# USB_-_UART_link.net
KiCad netlist of a schematic drawn in EAGLE
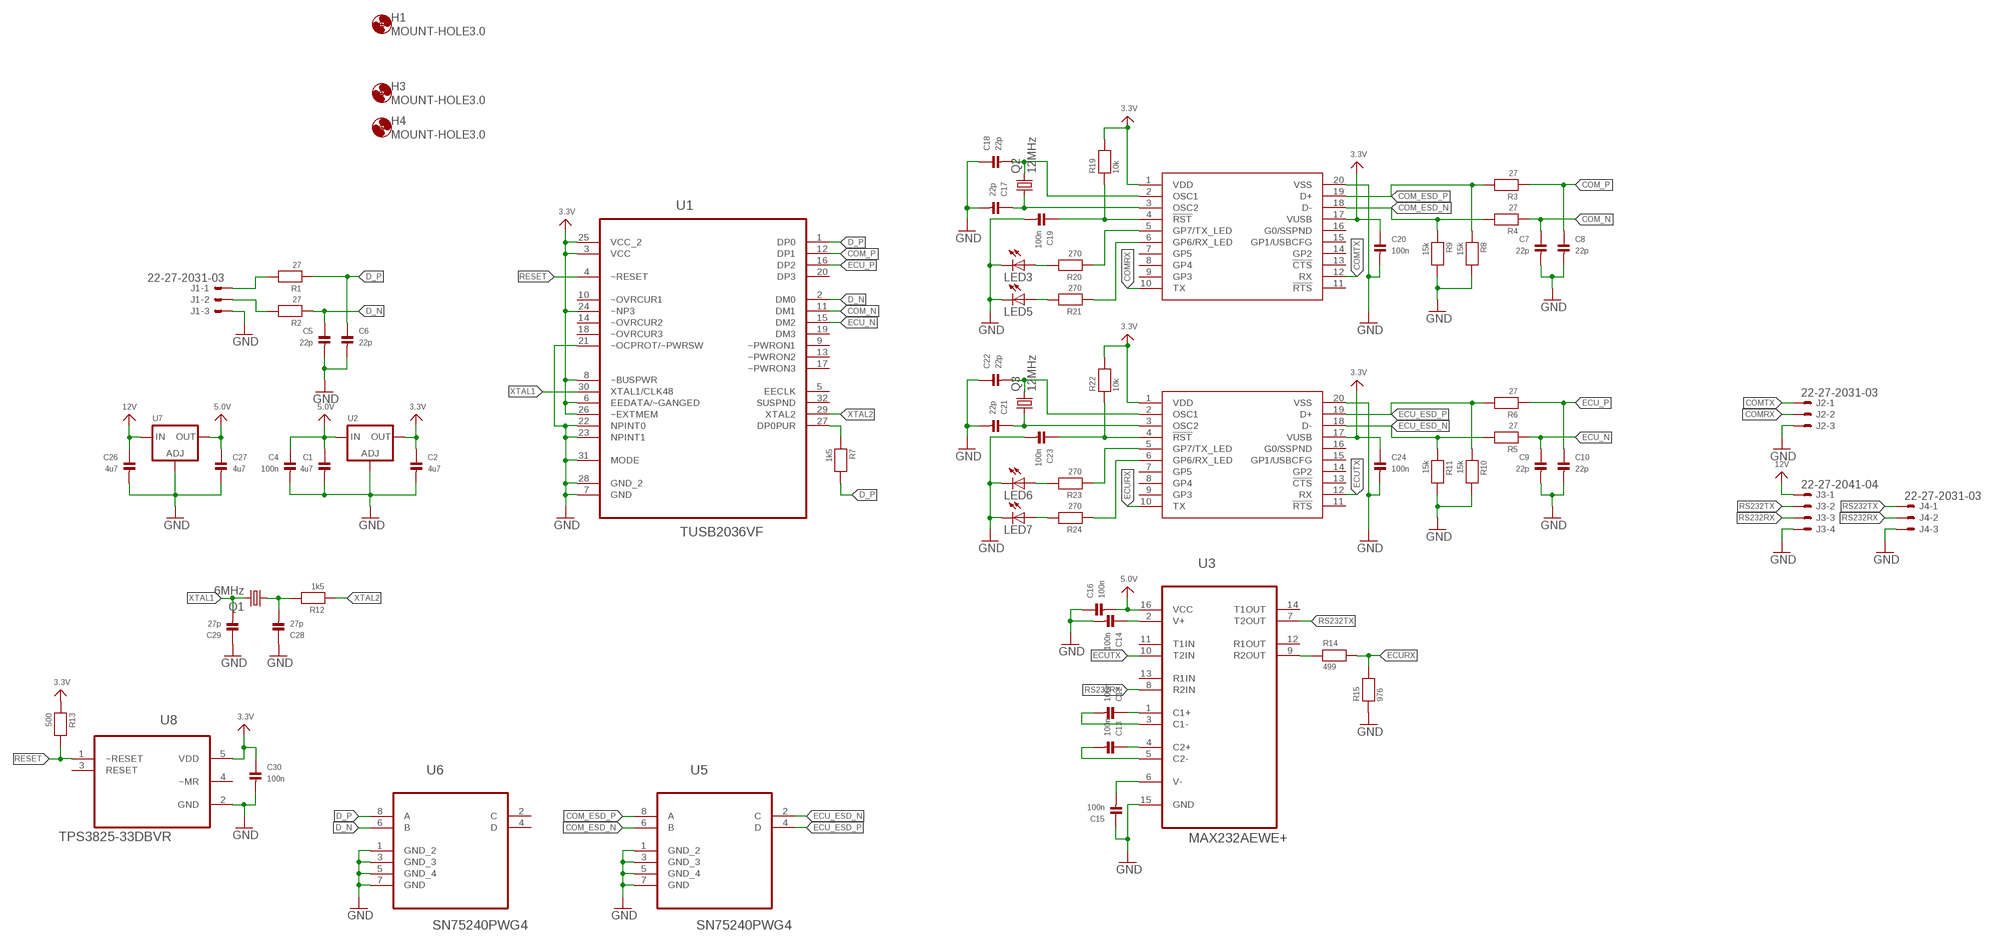
[diagram p0: schematic, sheet 1]

(export (version "E")
  (design (tool "Eeschema 10.0.6"))
  (components
    (comp (ref "C1")
      (value "4u7")
      (footprint "eagle-import:_0805")
      (libsource (lib "eagle-import") (part "CAP_CERAMIC_0805"))
    )
    (comp (ref "C2")
      (value "4u7")
      (footprint "eagle-import:_0805")
      (libsource (lib "eagle-import") (part "CAP_CERAMIC_0805"))
    )
    (comp (ref "C4")
      (value "100n")
      (footprint "eagle-import:_0603")
      (libsource (lib "eagle-import") (part "CAP_CERAMIC_0603"))
    )
    (comp (ref "C5")
      (value "22p")
      (footprint "eagle-import:_0603")
      (libsource (lib "eagle-import") (part "CAP_CERAMIC_0603"))
    )
    (comp (ref "C6")
      (value "22p")
      (footprint "eagle-import:_0603")
      (libsource (lib "eagle-import") (part "CAP_CERAMIC_0603"))
    )
    (comp (ref "C7")
      (value "22p")
      (footprint "eagle-import:_0603")
      (libsource (lib "eagle-import") (part "CAP_CERAMIC_0603"))
    )
    (comp (ref "C8")
      (value "22p")
      (footprint "eagle-import:_0603")
      (libsource (lib "eagle-import") (part "CAP_CERAMIC_0603"))
    )
    (comp (ref "C9")
      (value "22p")
      (footprint "eagle-import:_0603")
      (libsource (lib "eagle-import") (part "CAP_CERAMIC_0603"))
    )
    (comp (ref "C10")
      (value "22p")
      (footprint "eagle-import:_0603")
      (libsource (lib "eagle-import") (part "CAP_CERAMIC_0603"))
    )
    (comp (ref "C12")
      (value "100n")
      (footprint "eagle-import:_0603")
      (libsource (lib "eagle-import") (part "CAP_CERAMIC_0603"))
    )
    (comp (ref "C13")
      (value "100n")
      (footprint "eagle-import:_0603")
      (libsource (lib "eagle-import") (part "CAP_CERAMIC_0603"))
    )
    (comp (ref "C14")
      (value "100n")
      (footprint "eagle-import:_0603")
      (libsource (lib "eagle-import") (part "CAP_CERAMIC_0603"))
    )
    (comp (ref "C15")
      (value "100n")
      (footprint "eagle-import:_0603")
      (libsource (lib "eagle-import") (part "CAP_CERAMIC_0603"))
    )
    (comp (ref "C16")
      (value "100n")
      (footprint "eagle-import:_0603")
      (libsource (lib "eagle-import") (part "CAP_CERAMIC_0603"))
    )
    (comp (ref "C17")
      (value "22p")
      (footprint "eagle-import:_0603")
      (libsource (lib "eagle-import") (part "CAP_CERAMIC_0603"))
    )
    (comp (ref "C18")
      (value "22p")
      (footprint "eagle-import:_0603")
      (libsource (lib "eagle-import") (part "CAP_CERAMIC_0603"))
    )
    (comp (ref "C19")
      (value "100n")
      (footprint "eagle-import:_0603")
      (libsource (lib "eagle-import") (part "CAP_CERAMIC_0603"))
    )
    (comp (ref "C20")
      (value "100n")
      (footprint "eagle-import:_0603")
      (libsource (lib "eagle-import") (part "CAP_CERAMIC_0603"))
    )
    (comp (ref "C21")
      (value "22p")
      (footprint "eagle-import:_0603")
      (libsource (lib "eagle-import") (part "CAP_CERAMIC_0603"))
    )
    (comp (ref "C22")
      (value "22p")
      (footprint "eagle-import:_0603")
      (libsource (lib "eagle-import") (part "CAP_CERAMIC_0603"))
    )
    (comp (ref "C23")
      (value "100n")
      (footprint "eagle-import:_0603")
      (libsource (lib "eagle-import") (part "CAP_CERAMIC_0603"))
    )
    (comp (ref "C24")
      (value "100n")
      (footprint "eagle-import:_0603")
      (libsource (lib "eagle-import") (part "CAP_CERAMIC_0603"))
    )
    (comp (ref "C26")
      (value "4u7")
      (footprint "eagle-import:_0805")
      (libsource (lib "eagle-import") (part "CAP_CERAMIC_0805"))
    )
    (comp (ref "C27")
      (value "4u7")
      (footprint "eagle-import:_0805")
      (libsource (lib "eagle-import") (part "CAP_CERAMIC_0805"))
    )
    (comp (ref "C28")
      (value "27p")
      (footprint "eagle-import:_0603")
      (libsource (lib "eagle-import") (part "CAP_CERAMIC_0603"))
    )
    (comp (ref "C29")
      (value "27p")
      (footprint "eagle-import:_0603")
      (libsource (lib "eagle-import") (part "CAP_CERAMIC_0603"))
    )
    (comp (ref "C30")
      (value "100n")
      (footprint "eagle-import:_0603")
      (libsource (lib "eagle-import") (part "CAP_CERAMIC_0603"))
    )
    (comp (ref "H1")
      (value "MOUNT-HOLE3.0")
      (footprint "eagle-import:3,0")
      (libsource (lib "eagle-import") (part "MOUNT-HOLE3.0"))
    )
    (comp (ref "H3")
      (value "MOUNT-HOLE3.0")
      (footprint "eagle-import:3,0")
      (libsource (lib "eagle-import") (part "MOUNT-HOLE3.0"))
    )
    (comp (ref "H4")
      (value "MOUNT-HOLE3.0")
      (footprint "eagle-import:3,0")
      (libsource (lib "eagle-import") (part "MOUNT-HOLE3.0"))
    )
    (comp (ref "J1")
      (value "22-27-2031-03")
      (footprint "eagle-import:6410-03")
      (libsource (lib "eagle-import") (part "22-?-0327-2031"))
    )
    (comp (ref "J2")
      (value "22-27-2031-03")
      (footprint "eagle-import:6410-03")
      (libsource (lib "eagle-import") (part "22-?-0327-2031"))
    )
    (comp (ref "J3")
      (value "22-27-2041-04")
      (footprint "eagle-import:6410-04")
      (libsource (lib "eagle-import") (part "22-?-0427-2041"))
    )
    (comp (ref "J4")
      (value "22-27-2031-03")
      (footprint "eagle-import:6410-03")
      (libsource (lib "eagle-import") (part "22-?-0327-2031"))
    )
    (comp (ref "LED3")
      (value "LEDCHIPLED_0805")
      (footprint "eagle-import:CHIPLED_0805")
      (libsource (lib "eagle-import") (part "LEDCHIPLED_0805"))
    )
    (comp (ref "LED5")
      (value "LEDCHIPLED_0805")
      (footprint "eagle-import:CHIPLED_0805")
      (libsource (lib "eagle-import") (part "LEDCHIPLED_0805"))
    )
    (comp (ref "LED6")
      (value "LEDCHIPLED_0805")
      (footprint "eagle-import:CHIPLED_0805")
      (libsource (lib "eagle-import") (part "LEDCHIPLED_0805"))
    )
    (comp (ref "LED7")
      (value "LEDCHIPLED_0805")
      (footprint "eagle-import:CHIPLED_0805")
      (libsource (lib "eagle-import") (part "LEDCHIPLED_0805"))
    )
    (comp (ref "Q1")
      (value "6MHz")
      (footprint "eagle-import:HC49_S")
      (libsource (lib "eagle-import") (part "CRYSTALHC49S"))
    )
    (comp (ref "Q2")
      (value "12MHz")
      (footprint "eagle-import:HC49_S")
      (libsource (lib "eagle-import") (part "CRYSTALHC49S"))
    )
    (comp (ref "Q3")
      (value "12MHz")
      (footprint "eagle-import:HC49_S")
      (libsource (lib "eagle-import") (part "CRYSTALHC49S"))
    )
    (comp (ref "R1")
      (value "27")
      (footprint "eagle-import:_0603")
      (libsource (lib "eagle-import") (part "RESISTOR_0603"))
    )
    (comp (ref "R2")
      (value "27")
      (footprint "eagle-import:_0603")
      (libsource (lib "eagle-import") (part "RESISTOR_0603"))
    )
    (comp (ref "R3")
      (value "27")
      (footprint "eagle-import:_0603")
      (libsource (lib "eagle-import") (part "RESISTOR_0603"))
    )
    (comp (ref "R4")
      (value "27")
      (footprint "eagle-import:_0603")
      (libsource (lib "eagle-import") (part "RESISTOR_0603"))
    )
    (comp (ref "R5")
      (value "27")
      (footprint "eagle-import:_0603")
      (libsource (lib "eagle-import") (part "RESISTOR_0603"))
    )
    (comp (ref "R6")
      (value "27")
      (footprint "eagle-import:_0603")
      (libsource (lib "eagle-import") (part "RESISTOR_0603"))
    )
    (comp (ref "R7")
      (value "1k5")
      (footprint "eagle-import:_0603")
      (libsource (lib "eagle-import") (part "RESISTOR_0603"))
    )
    (comp (ref "R8")
      (value "15k")
      (footprint "eagle-import:_0603")
      (libsource (lib "eagle-import") (part "RESISTOR_0603"))
    )
    (comp (ref "R9")
      (value "15k")
      (footprint "eagle-import:_0603")
      (libsource (lib "eagle-import") (part "RESISTOR_0603"))
    )
    (comp (ref "R10")
      (value "15k")
      (footprint "eagle-import:_0603")
      (libsource (lib "eagle-import") (part "RESISTOR_0603"))
    )
    (comp (ref "R11")
      (value "15k")
      (footprint "eagle-import:_0603")
      (libsource (lib "eagle-import") (part "RESISTOR_0603"))
    )
    (comp (ref "R12")
      (value "1k5")
      (footprint "eagle-import:_0603")
      (libsource (lib "eagle-import") (part "RESISTOR_0603"))
    )
    (comp (ref "R13")
      (value "500")
      (footprint "eagle-import:_0603")
      (libsource (lib "eagle-import") (part "RESISTOR_0603"))
    )
    (comp (ref "R14")
      (value "499")
      (footprint "eagle-import:_0603")
      (libsource (lib "eagle-import") (part "RESISTOR_0603"))
    )
    (comp (ref "R15")
      (value "976")
      (footprint "eagle-import:_0603")
      (libsource (lib "eagle-import") (part "RESISTOR_0603"))
    )
    (comp (ref "R19")
      (value "10k")
      (footprint "eagle-import:_0603")
      (libsource (lib "eagle-import") (part "RESISTOR_0603"))
    )
    (comp (ref "R20")
      (value "270")
      (footprint "eagle-import:_0603")
      (libsource (lib "eagle-import") (part "RESISTOR_0603"))
    )
    (comp (ref "R21")
      (value "270")
      (footprint "eagle-import:_0603")
      (libsource (lib "eagle-import") (part "RESISTOR_0603"))
    )
    (comp (ref "R22")
      (value "10k")
      (footprint "eagle-import:_0603")
      (libsource (lib "eagle-import") (part "RESISTOR_0603"))
    )
    (comp (ref "R23")
      (value "270")
      (footprint "eagle-import:_0603")
      (libsource (lib "eagle-import") (part "RESISTOR_0603"))
    )
    (comp (ref "R24")
      (value "270")
      (footprint "eagle-import:_0603")
      (libsource (lib "eagle-import") (part "RESISTOR_0603"))
    )
    (comp (ref "U$24")
      (value "MCP2200")
      (footprint "eagle-import:SO20L")
      (libsource (lib "eagle-import") (part "MCP2200"))
    )
    (comp (ref "U$29")
      (value "MCP2200")
      (footprint "eagle-import:SO20L")
      (libsource (lib "eagle-import") (part "MCP2200"))
    )
    (comp (ref "U1")
      (value "TUSB2036VF")
      (footprint "eagle-import:QFP80P900X900X145-32N")
      (libsource (lib "eagle-import") (part "TUSB2036VF"))
    )
    (comp (ref "U2")
      (value "LM1117SOT223-REFLOW")
      (footprint "eagle-import:SOT223-R")
      (libsource (lib "eagle-import") (part "LM1117SOT223-REFLOW"))
    )
    (comp (ref "U3")
      (value "MAX232AEWE+")
      (footprint "eagle-import:SOIC127P1032X265-16N")
      (libsource (lib "eagle-import") (part "MAX232AEWE+"))
    )
    (comp (ref "U5")
      (value "SN75240PWG4")
      (footprint "eagle-import:SOP65P640X120-8N")
      (libsource (lib "eagle-import") (part "SN75240PWG4"))
    )
    (comp (ref "U6")
      (value "SN75240PWG4")
      (footprint "eagle-import:SOP65P640X120-8N")
      (libsource (lib "eagle-import") (part "SN75240PWG4"))
    )
    (comp (ref "U7")
      (value "LM1117SOT223-REFLOW")
      (footprint "eagle-import:SOT223-R")
      (libsource (lib "eagle-import") (part "LM1117SOT223-REFLOW"))
    )
    (comp (ref "U8")
      (value "TPS3825-33DBVR")
      (footprint "eagle-import:SOT95P280X145-5N")
      (libsource (lib "eagle-import") (part "TPS3825-33DBVR"))
    )
  )
  (nets
    (net (code "1") (name "3.3V") (class "Default")
      (node (ref "C2") (pin "1") (pinfunction "P$1_1") (pintype "passive"))
      (node (ref "C20") (pin "1") (pinfunction "P$1_1") (pintype "passive"))
      (node (ref "C24") (pin "1") (pinfunction "P$1_1") (pintype "passive"))
      (node (ref "C30") (pin "1") (pinfunction "P$1_1") (pintype "passive"))
      (node (ref "R13") (pin "1") (pinfunction "1_1") (pintype "passive"))
      (node (ref "R19") (pin "2") (pinfunction "2_2") (pintype "passive"))
      (node (ref "R22") (pin "2") (pinfunction "2_2") (pintype "passive"))
      (node (ref "U$24") (pin "1") (pinfunction "VDD_1") (pintype "bidirectional"))
      (node (ref "U$24") (pin "17") (pinfunction "VUSB_17") (pintype "bidirectional"))
      (node (ref "U$29") (pin "1") (pinfunction "VDD_1") (pintype "bidirectional"))
      (node (ref "U$29") (pin "17") (pinfunction "VUSB_17") (pintype "bidirectional"))
      (node (ref "U1") (pin "24") (pinfunction "~{NP3}_24") (pintype "input"))
      (node (ref "U1") (pin "25") (pinfunction "VCC_2_25") (pintype "power_in"))
      (node (ref "U1") (pin "26") (pinfunction "~{EXTMEM}_26") (pintype "input"))
      (node (ref "U1") (pin "3") (pinfunction "VCC_3") (pintype "power_in"))
      (node (ref "U1") (pin "6") (pinfunction "EEDATA/~{GANGED}_6") (pintype "bidirectional"))
      (node (ref "U1") (pin "8") (pinfunction "~{BUSPWR}_8") (pintype "input"))
      (node (ref "U2") (pin "2") (pinfunction "OUT_2") (pintype "passive"))
      (node (ref "U8") (pin "5") (pinfunction "VDD_5") (pintype "power_in"))
    )
    (net (code "2") (name "5.0V") (class "Default")
      (node (ref "C1") (pin "1") (pinfunction "P$1_1") (pintype "passive"))
      (node (ref "C16") (pin "2") (pinfunction "P$2_2") (pintype "passive"))
      (node (ref "C27") (pin "1") (pinfunction "P$1_1") (pintype "passive"))
      (node (ref "C4") (pin "1") (pinfunction "P$1_1") (pintype "passive"))
      (node (ref "U2") (pin "3") (pinfunction "IN_3") (pintype "input"))
      (node (ref "U3") (pin "16") (pinfunction "VCC_16") (pintype "power_in"))
      (node (ref "U7") (pin "2") (pinfunction "OUT_2") (pintype "passive"))
    )
    (net (code "3") (name "12V") (class "Default")
      (node (ref "C26") (pin "1") (pinfunction "P$1_1") (pintype "passive"))
      (node (ref "J3") (pin "1") (pinfunction "S_1") (pintype "passive"))
      (node (ref "U7") (pin "3") (pinfunction "IN_3") (pintype "input"))
    )
    (net (code "4") (name "COMRX") (class "Default")
      (node (ref "J2") (pin "2") (pinfunction "S_2") (pintype "passive"))
      (node (ref "U$24") (pin "10") (pinfunction "TX_10") (pintype "bidirectional"))
    )
    (net (code "5") (name "COMTX") (class "Default")
      (node (ref "J2") (pin "1") (pinfunction "S_1") (pintype "passive"))
      (node (ref "U$24") (pin "12") (pinfunction "RX_12") (pintype "bidirectional"))
    )
    (net (code "6") (name "COM_ESD_N") (class "Default")
      (node (ref "R4") (pin "2") (pinfunction "2_2") (pintype "passive"))
      (node (ref "R9") (pin "1") (pinfunction "1_1") (pintype "passive"))
      (node (ref "U$24") (pin "18") (pinfunction "D-_18") (pintype "bidirectional"))
      (node (ref "U5") (pin "6") (pinfunction "B_6") (pintype "passive"))
    )
    (net (code "7") (name "COM_ESD_P") (class "Default")
      (node (ref "R3") (pin "2") (pinfunction "2_2") (pintype "passive"))
      (node (ref "R8") (pin "1") (pinfunction "1_1") (pintype "passive"))
      (node (ref "U$24") (pin "19") (pinfunction "D+_19") (pintype "bidirectional"))
      (node (ref "U5") (pin "8") (pinfunction "A_8") (pintype "passive"))
    )
    (net (code "8") (name "COM_N") (class "Default")
      (node (ref "C7") (pin "1") (pinfunction "P$1_1") (pintype "passive"))
      (node (ref "R4") (pin "1") (pinfunction "1_1") (pintype "passive"))
      (node (ref "U1") (pin "11") (pinfunction "DM1_11") (pintype "bidirectional"))
    )
    (net (code "9") (name "COM_P") (class "Default")
      (node (ref "C8") (pin "1") (pinfunction "P$1_1") (pintype "passive"))
      (node (ref "R3") (pin "1") (pinfunction "1_1") (pintype "passive"))
      (node (ref "U1") (pin "12") (pinfunction "DP1_12") (pintype "bidirectional"))
    )
    (net (code "10") (name "D_N") (class "Default")
      (node (ref "C5") (pin "1") (pinfunction "P$1_1") (pintype "passive"))
      (node (ref "R2") (pin "1") (pinfunction "1_1") (pintype "passive"))
      (node (ref "U1") (pin "2") (pinfunction "DM0_2") (pintype "bidirectional"))
      (node (ref "U6") (pin "6") (pinfunction "B_6") (pintype "passive"))
    )
    (net (code "11") (name "D_P") (class "Default")
      (node (ref "C6") (pin "1") (pinfunction "P$1_1") (pintype "passive"))
      (node (ref "R1") (pin "1") (pinfunction "1_1") (pintype "passive"))
      (node (ref "R7") (pin "2") (pinfunction "2_2") (pintype "passive"))
      (node (ref "U1") (pin "1") (pinfunction "DP0_1") (pintype "bidirectional"))
      (node (ref "U6") (pin "8") (pinfunction "A_8") (pintype "passive"))
    )
    (net (code "12") (name "ECURX") (class "Default")
      (node (ref "R14") (pin "2") (pinfunction "2_2") (pintype "passive"))
      (node (ref "R15") (pin "2") (pinfunction "2_2") (pintype "passive"))
      (node (ref "U$29") (pin "10") (pinfunction "TX_10") (pintype "bidirectional"))
    )
    (net (code "13") (name "ECUTX") (class "Default")
      (node (ref "U$29") (pin "12") (pinfunction "RX_12") (pintype "bidirectional"))
      (node (ref "U3") (pin "10") (pinfunction "T2IN_10") (pintype "input"))
    )
    (net (code "14") (name "ECU_ESD_N") (class "Default")
      (node (ref "R11") (pin "1") (pinfunction "1_1") (pintype "passive"))
      (node (ref "R5") (pin "2") (pinfunction "2_2") (pintype "passive"))
      (node (ref "U$29") (pin "18") (pinfunction "D-_18") (pintype "bidirectional"))
      (node (ref "U5") (pin "2") (pinfunction "C_2") (pintype "passive"))
    )
    (net (code "15") (name "ECU_ESD_P") (class "Default")
      (node (ref "R10") (pin "1") (pinfunction "1_1") (pintype "passive"))
      (node (ref "R6") (pin "2") (pinfunction "2_2") (pintype "passive"))
      (node (ref "U$29") (pin "19") (pinfunction "D+_19") (pintype "bidirectional"))
      (node (ref "U5") (pin "4") (pinfunction "D_4") (pintype "passive"))
    )
    (net (code "16") (name "ECU_N") (class "Default")
      (node (ref "C9") (pin "1") (pinfunction "P$1_1") (pintype "passive"))
      (node (ref "R5") (pin "1") (pinfunction "1_1") (pintype "passive"))
      (node (ref "U1") (pin "15") (pinfunction "DM2_15") (pintype "bidirectional"))
    )
    (net (code "17") (name "ECU_P") (class "Default")
      (node (ref "C10") (pin "1") (pinfunction "P$1_1") (pintype "passive"))
      (node (ref "R6") (pin "1") (pinfunction "1_1") (pintype "passive"))
      (node (ref "U1") (pin "16") (pinfunction "DP2_16") (pintype "bidirectional"))
    )
    (net (code "18") (name "GND") (class "Default")
      (node (ref "C1") (pin "2") (pinfunction "P$2_2") (pintype "passive"))
      (node (ref "C10") (pin "2") (pinfunction "P$2_2") (pintype "passive"))
      (node (ref "C14") (pin "2") (pinfunction "P$2_2") (pintype "passive"))
      (node (ref "C15") (pin "1") (pinfunction "P$1_1") (pintype "passive"))
      (node (ref "C16") (pin "1") (pinfunction "P$1_1") (pintype "passive"))
      (node (ref "C17") (pin "2") (pinfunction "P$2_2") (pintype "passive"))
      (node (ref "C18") (pin "1") (pinfunction "P$1_1") (pintype "passive"))
      (node (ref "C19") (pin "2") (pinfunction "P$2_2") (pintype "passive"))
      (node (ref "C2") (pin "2") (pinfunction "P$2_2") (pintype "passive"))
      (node (ref "C20") (pin "2") (pinfunction "P$2_2") (pintype "passive"))
      (node (ref "C21") (pin "2") (pinfunction "P$2_2") (pintype "passive"))
      (node (ref "C22") (pin "1") (pinfunction "P$1_1") (pintype "passive"))
      (node (ref "C23") (pin "2") (pinfunction "P$2_2") (pintype "passive"))
      (node (ref "C24") (pin "2") (pinfunction "P$2_2") (pintype "passive"))
      (node (ref "C26") (pin "2") (pinfunction "P$2_2") (pintype "passive"))
      (node (ref "C27") (pin "2") (pinfunction "P$2_2") (pintype "passive"))
      (node (ref "C28") (pin "1") (pinfunction "P$1_1") (pintype "passive"))
      (node (ref "C29") (pin "1") (pinfunction "P$1_1") (pintype "passive"))
      (node (ref "C30") (pin "2") (pinfunction "P$2_2") (pintype "passive"))
      (node (ref "C4") (pin "2") (pinfunction "P$2_2") (pintype "passive"))
      (node (ref "C5") (pin "2") (pinfunction "P$2_2") (pintype "passive"))
      (node (ref "C6") (pin "2") (pinfunction "P$2_2") (pintype "passive"))
      (node (ref "C7") (pin "2") (pinfunction "P$2_2") (pintype "passive"))
      (node (ref "C8") (pin "2") (pinfunction "P$2_2") (pintype "passive"))
      (node (ref "C9") (pin "2") (pinfunction "P$2_2") (pintype "passive"))
      (node (ref "J1") (pin "3") (pinfunction "S_3") (pintype "passive"))
      (node (ref "J2") (pin "3") (pinfunction "S_3") (pintype "passive"))
      (node (ref "J3") (pin "4") (pinfunction "S_4") (pintype "passive"))
      (node (ref "J4") (pin "3") (pinfunction "S_3") (pintype "passive"))
      (node (ref "LED3") (pin "C") (pinfunction "C_C") (pintype "passive"))
      (node (ref "LED5") (pin "C") (pinfunction "C_C") (pintype "passive"))
      (node (ref "LED6") (pin "C") (pinfunction "C_C") (pintype "passive"))
      (node (ref "LED7") (pin "C") (pinfunction "C_C") (pintype "passive"))
      (node (ref "R10") (pin "2") (pinfunction "2_2") (pintype "passive"))
      (node (ref "R11") (pin "2") (pinfunction "2_2") (pintype "passive"))
      (node (ref "R15") (pin "1") (pinfunction "1_1") (pintype "passive"))
      (node (ref "R8") (pin "2") (pinfunction "2_2") (pintype "passive"))
      (node (ref "R9") (pin "2") (pinfunction "2_2") (pintype "passive"))
      (node (ref "U$24") (pin "20") (pinfunction "VSS_20") (pintype "bidirectional"))
      (node (ref "U$29") (pin "20") (pinfunction "VSS_20") (pintype "bidirectional"))
      (node (ref "U1") (pin "21") (pinfunction "~{OCPROT/}PWRSW_21") (pintype "input"))
      (node (ref "U1") (pin "22") (pinfunction "NPINT0_22") (pintype "input"))
      (node (ref "U1") (pin "23") (pinfunction "NPINT1_23") (pintype "input"))
      (node (ref "U1") (pin "28") (pinfunction "GND_2_28") (pintype "passive"))
      (node (ref "U1") (pin "31") (pinfunction "MODE_31") (pintype "input"))
      (node (ref "U1") (pin "7") (pinfunction "GND_7") (pintype "passive"))
      (node (ref "U2") (pin "1") (pinfunction "ADJ_1") (pintype "input"))
      (node (ref "U3") (pin "15") (pinfunction "GND_15") (pintype "passive"))
      (node (ref "U5") (pin "1") (pinfunction "GND_2_1") (pintype "passive"))
      (node (ref "U5") (pin "3") (pinfunction "GND_3_3") (pintype "passive"))
      (node (ref "U5") (pin "5") (pinfunction "GND_4_5") (pintype "passive"))
      (node (ref "U5") (pin "7") (pinfunction "GND_7") (pintype "passive"))
      (node (ref "U6") (pin "1") (pinfunction "GND_2_1") (pintype "passive"))
      (node (ref "U6") (pin "3") (pinfunction "GND_3_3") (pintype "passive"))
      (node (ref "U6") (pin "5") (pinfunction "GND_4_5") (pintype "passive"))
      (node (ref "U6") (pin "7") (pinfunction "GND_7") (pintype "passive"))
      (node (ref "U7") (pin "1") (pinfunction "ADJ_1") (pintype "input"))
      (node (ref "U8") (pin "2") (pinfunction "GND_2") (pintype "passive"))
    )
    (net (code "19") (name "Net-(C12-P$1)") (class "Default")
      (node (ref "C12") (pin "1") (pinfunction "P$1_1") (pintype "passive"))
      (node (ref "U3") (pin "1") (pinfunction "C1+_1") (pintype "input"))
    )
    (net (code "20") (name "Net-(C12-P$2)") (class "Default")
      (node (ref "C12") (pin "2") (pinfunction "P$2_2") (pintype "passive"))
      (node (ref "U3") (pin "3") (pinfunction "C1-_3") (pintype "input"))
    )
    (net (code "21") (name "Net-(C13-P$1)") (class "Default")
      (node (ref "C13") (pin "1") (pinfunction "P$1_1") (pintype "passive"))
      (node (ref "U3") (pin "4") (pinfunction "C2+_4") (pintype "input"))
    )
    (net (code "22") (name "Net-(C13-P$2)") (class "Default")
      (node (ref "C13") (pin "2") (pinfunction "P$2_2") (pintype "passive"))
      (node (ref "U3") (pin "5") (pinfunction "C2-_5") (pintype "input"))
    )
    (net (code "23") (name "Net-(C14-P$1)") (class "Default")
      (node (ref "C14") (pin "1") (pinfunction "P$1_1") (pintype "passive"))
      (node (ref "U3") (pin "2") (pinfunction "V+_2") (pintype "power_in"))
    )
    (net (code "24") (name "Net-(C15-P$2)") (class "Default")
      (node (ref "C15") (pin "2") (pinfunction "P$2_2") (pintype "passive"))
      (node (ref "U3") (pin "6") (pinfunction "V-_6") (pintype "power_in"))
    )
    (net (code "25") (name "Net-(C17-P$1)") (class "Default")
      (node (ref "C17") (pin "1") (pinfunction "P$1_1") (pintype "passive"))
      (node (ref "Q2") (pin "1") (pinfunction "1_1") (pintype "passive"))
      (node (ref "U$24") (pin "3") (pinfunction "OSC2_3") (pintype "bidirectional"))
    )
    (net (code "26") (name "Net-(C18-P$2)") (class "Default")
      (node (ref "C18") (pin "2") (pinfunction "P$2_2") (pintype "passive"))
      (node (ref "Q2") (pin "2") (pinfunction "2_2") (pintype "passive"))
      (node (ref "U$24") (pin "2") (pinfunction "OSC1_2") (pintype "bidirectional"))
    )
    (net (code "27") (name "Net-(C19-P$1)") (class "Default")
      (node (ref "C19") (pin "1") (pinfunction "P$1_1") (pintype "passive"))
      (node (ref "R19") (pin "1") (pinfunction "1_1") (pintype "passive"))
      (node (ref "U$24") (pin "4") (pinfunction "~{RST}_4") (pintype "bidirectional"))
    )
    (net (code "28") (name "Net-(C21-P$1)") (class "Default")
      (node (ref "C21") (pin "1") (pinfunction "P$1_1") (pintype "passive"))
      (node (ref "Q3") (pin "1") (pinfunction "1_1") (pintype "passive"))
      (node (ref "U$29") (pin "3") (pinfunction "OSC2_3") (pintype "bidirectional"))
    )
    (net (code "29") (name "Net-(C22-P$2)") (class "Default")
      (node (ref "C22") (pin "2") (pinfunction "P$2_2") (pintype "passive"))
      (node (ref "Q3") (pin "2") (pinfunction "2_2") (pintype "passive"))
      (node (ref "U$29") (pin "2") (pinfunction "OSC1_2") (pintype "bidirectional"))
    )
    (net (code "30") (name "Net-(C23-P$1)") (class "Default")
      (node (ref "C23") (pin "1") (pinfunction "P$1_1") (pintype "passive"))
      (node (ref "R22") (pin "1") (pinfunction "1_1") (pintype "passive"))
      (node (ref "U$29") (pin "4") (pinfunction "~{RST}_4") (pintype "bidirectional"))
    )
    (net (code "31") (name "Net-(C28-P$2)") (class "Default")
      (node (ref "C28") (pin "2") (pinfunction "P$2_2") (pintype "passive"))
      (node (ref "Q1") (pin "1") (pinfunction "1_1") (pintype "passive"))
      (node (ref "R12") (pin "2") (pinfunction "2_2") (pintype "passive"))
    )
    (net (code "32") (name "Net-(J1A-S)") (class "Default")
      (node (ref "J1") (pin "1") (pinfunction "S_1") (pintype "passive"))
      (node (ref "R1") (pin "2") (pinfunction "2_2") (pintype "passive"))
    )
    (net (code "33") (name "Net-(J1B-S)") (class "Default")
      (node (ref "J1") (pin "2") (pinfunction "S_2") (pintype "passive"))
      (node (ref "R2") (pin "2") (pinfunction "2_2") (pintype "passive"))
    )
    (net (code "34") (name "Net-(LED3-PadA)") (class "Default")
      (node (ref "LED3") (pin "A") (pinfunction "A_A") (pintype "passive"))
      (node (ref "R20") (pin "2") (pinfunction "2_2") (pintype "passive"))
    )
    (net (code "35") (name "Net-(LED5-PadA)") (class "Default")
      (node (ref "LED5") (pin "A") (pinfunction "A_A") (pintype "passive"))
      (node (ref "R21") (pin "2") (pinfunction "2_2") (pintype "passive"))
    )
    (net (code "36") (name "Net-(LED6-PadA)") (class "Default")
      (node (ref "LED6") (pin "A") (pinfunction "A_A") (pintype "passive"))
      (node (ref "R23") (pin "2") (pinfunction "2_2") (pintype "passive"))
    )
    (net (code "37") (name "Net-(LED7-PadA)") (class "Default")
      (node (ref "LED7") (pin "A") (pinfunction "A_A") (pintype "passive"))
      (node (ref "R24") (pin "2") (pinfunction "2_2") (pintype "passive"))
    )
    (net (code "38") (name "Net-(U$24-GP6{slash}RX_LED)") (class "Default")
      (node (ref "R21") (pin "1") (pinfunction "1_1") (pintype "passive"))
      (node (ref "U$24") (pin "6") (pinfunction "GP6/RX_LED_6") (pintype "bidirectional"))
    )
    (net (code "39") (name "Net-(U$24-GP7{slash}TX_LED)") (class "Default")
      (node (ref "R20") (pin "1") (pinfunction "1_1") (pintype "passive"))
      (node (ref "U$24") (pin "5") (pinfunction "GP7/TX_LED_5") (pintype "bidirectional"))
    )
    (net (code "40") (name "Net-(U$29-GP6{slash}RX_LED)") (class "Default")
      (node (ref "R24") (pin "1") (pinfunction "1_1") (pintype "passive"))
      (node (ref "U$29") (pin "6") (pinfunction "GP6/RX_LED_6") (pintype "bidirectional"))
    )
    (net (code "41") (name "Net-(U$29-GP7{slash}TX_LED)") (class "Default")
      (node (ref "R23") (pin "1") (pinfunction "1_1") (pintype "passive"))
      (node (ref "U$29") (pin "5") (pinfunction "GP7/TX_LED_5") (pintype "bidirectional"))
    )
    (net (code "42") (name "Net-(U1-DP0PUR)") (class "Default")
      (node (ref "R7") (pin "1") (pinfunction "1_1") (pintype "passive"))
      (node (ref "U1") (pin "27") (pinfunction "DP0PUR_27") (pintype "output"))
    )
    (net (code "43") (name "Net-(U3-R2OUT)") (class "Default")
      (node (ref "R14") (pin "1") (pinfunction "1_1") (pintype "passive"))
      (node (ref "U3") (pin "9") (pinfunction "R2OUT_9") (pintype "output"))
    )
    (net (code "44") (name "RESET") (class "Default")
      (node (ref "R13") (pin "2") (pinfunction "2_2") (pintype "passive"))
      (node (ref "U1") (pin "4") (pinfunction "~{RESET}_4") (pintype "input"))
      (node (ref "U8") (pin "1") (pinfunction "~{RESET}_1") (pintype "output"))
    )
    (net (code "45") (name "RS232RX") (class "Default")
      (node (ref "J3") (pin "3") (pinfunction "S_3") (pintype "passive"))
      (node (ref "J4") (pin "2") (pinfunction "S_2") (pintype "passive"))
      (node (ref "U3") (pin "8") (pinfunction "R2IN_8") (pintype "input"))
    )
    (net (code "46") (name "RS232TX") (class "Default")
      (node (ref "J3") (pin "2") (pinfunction "S_2") (pintype "passive"))
      (node (ref "J4") (pin "1") (pinfunction "S_1") (pintype "passive"))
      (node (ref "U3") (pin "7") (pinfunction "T2OUT_7") (pintype "output"))
    )
    (net (code "47") (name "XTAL1") (class "Default")
      (node (ref "C29") (pin "2") (pinfunction "P$2_2") (pintype "passive"))
      (node (ref "Q1") (pin "2") (pinfunction "2_2") (pintype "passive"))
      (node (ref "U1") (pin "30") (pinfunction "XTAL1/CLK48_30") (pintype "input"))
    )
    (net (code "48") (name "XTAL2") (class "Default")
      (node (ref "R12") (pin "1") (pinfunction "1_1") (pintype "passive"))
      (node (ref "U1") (pin "29") (pinfunction "XTAL2_29") (pintype "output"))
    )
    (net (code "49") (name "unconnected-(U$24-G0{slash}SSPND-Pad16)") (class "Default")
      (node (ref "U$24") (pin "16") (pinfunction "G0/SSPND_16") (pintype "bidirectional"))
    )
    (net (code "50") (name "unconnected-(U$24-GP1{slash}USBCFG-Pad15)") (class "Default")
      (node (ref "U$24") (pin "15") (pinfunction "GP1/USBCFG_15") (pintype "bidirectional"))
    )
    (net (code "51") (name "unconnected-(U$24-GP2-Pad14)") (class "Default")
      (node (ref "U$24") (pin "14") (pinfunction "GP2_14") (pintype "bidirectional"))
    )
    (net (code "52") (name "unconnected-(U$24-GP3-Pad9)") (class "Default")
      (node (ref "U$24") (pin "9") (pinfunction "GP3_9") (pintype "bidirectional"))
    )
    (net (code "53") (name "unconnected-(U$24-GP4-Pad8)") (class "Default")
      (node (ref "U$24") (pin "8") (pinfunction "GP4_8") (pintype "bidirectional"))
    )
    (net (code "54") (name "unconnected-(U$24-GP5-Pad7)") (class "Default")
      (node (ref "U$24") (pin "7") (pinfunction "GP5_7") (pintype "bidirectional"))
    )
    (net (code "55") (name "unconnected-(U$24-~{CTS}-Pad13)") (class "Default")
      (node (ref "U$24") (pin "13") (pinfunction "~{CTS}_13") (pintype "bidirectional"))
    )
    (net (code "56") (name "unconnected-(U$24-~{RTS}-Pad11)") (class "Default")
      (node (ref "U$24") (pin "11") (pinfunction "~{RTS}_11") (pintype "bidirectional"))
    )
    (net (code "57") (name "unconnected-(U$29-G0{slash}SSPND-Pad16)") (class "Default")
      (node (ref "U$29") (pin "16") (pinfunction "G0/SSPND_16") (pintype "bidirectional"))
    )
    (net (code "58") (name "unconnected-(U$29-GP1{slash}USBCFG-Pad15)") (class "Default")
      (node (ref "U$29") (pin "15") (pinfunction "GP1/USBCFG_15") (pintype "bidirectional"))
    )
    (net (code "59") (name "unconnected-(U$29-GP2-Pad14)") (class "Default")
      (node (ref "U$29") (pin "14") (pinfunction "GP2_14") (pintype "bidirectional"))
    )
    (net (code "60") (name "unconnected-(U$29-GP3-Pad9)") (class "Default")
      (node (ref "U$29") (pin "9") (pinfunction "GP3_9") (pintype "bidirectional"))
    )
    (net (code "61") (name "unconnected-(U$29-GP4-Pad8)") (class "Default")
      (node (ref "U$29") (pin "8") (pinfunction "GP4_8") (pintype "bidirectional"))
    )
    (net (code "62") (name "unconnected-(U$29-GP5-Pad7)") (class "Default")
      (node (ref "U$29") (pin "7") (pinfunction "GP5_7") (pintype "bidirectional"))
    )
    (net (code "63") (name "unconnected-(U$29-~{CTS}-Pad13)") (class "Default")
      (node (ref "U$29") (pin "13") (pinfunction "~{CTS}_13") (pintype "bidirectional"))
    )
    (net (code "64") (name "unconnected-(U$29-~{RTS}-Pad11)") (class "Default")
      (node (ref "U$29") (pin "11") (pinfunction "~{RTS}_11") (pintype "bidirectional"))
    )
    (net (code "65") (name "unconnected-(U1-DM3-Pad19)") (class "Default")
      (node (ref "U1") (pin "19") (pinfunction "DM3_19") (pintype "bidirectional"))
    )
    (net (code "66") (name "unconnected-(U1-DP3-Pad20)") (class "Default")
      (node (ref "U1") (pin "20") (pinfunction "DP3_20") (pintype "bidirectional"))
    )
    (net (code "67") (name "unconnected-(U1-EECLK-Pad5)") (class "Default")
      (node (ref "U1") (pin "5") (pinfunction "EECLK_5") (pintype "output"))
    )
    (net (code "68") (name "unconnected-(U1-SUSPND-Pad32)") (class "Default")
      (node (ref "U1") (pin "32") (pinfunction "SUSPND_32") (pintype "output"))
    )
    (net (code "69") (name "unconnected-(U1-~{OVRCUR1}-Pad10)") (class "Default")
      (node (ref "U1") (pin "10") (pinfunction "~{OVRCUR1}_10") (pintype "input"))
    )
    (net (code "70") (name "unconnected-(U1-~{OVRCUR2}-Pad14)") (class "Default")
      (node (ref "U1") (pin "14") (pinfunction "~{OVRCUR2}_14") (pintype "input"))
    )
    (net (code "71") (name "unconnected-(U1-~{OVRCUR3}-Pad18)") (class "Default")
      (node (ref "U1") (pin "18") (pinfunction "~{OVRCUR3}_18") (pintype "input"))
    )
    (net (code "72") (name "unconnected-(U1-~{PWRON1}-Pad9)") (class "Default")
      (node (ref "U1") (pin "9") (pinfunction "~{PWRON1}_9") (pintype "output"))
    )
    (net (code "73") (name "unconnected-(U1-~{PWRON2}-Pad13)") (class "Default")
      (node (ref "U1") (pin "13") (pinfunction "~{PWRON2}_13") (pintype "output"))
    )
    (net (code "74") (name "unconnected-(U1-~{PWRON3}-Pad17)") (class "Default")
      (node (ref "U1") (pin "17") (pinfunction "~{PWRON3}_17") (pintype "output"))
    )
    (net (code "75") (name "unconnected-(U3-R1IN-Pad13)") (class "Default")
      (node (ref "U3") (pin "13") (pinfunction "R1IN_13") (pintype "input"))
    )
    (net (code "76") (name "unconnected-(U3-R1OUT-Pad12)") (class "Default")
      (node (ref "U3") (pin "12") (pinfunction "R1OUT_12") (pintype "output"))
    )
    (net (code "77") (name "unconnected-(U3-T1IN-Pad11)") (class "Default")
      (node (ref "U3") (pin "11") (pinfunction "T1IN_11") (pintype "input"))
    )
    (net (code "78") (name "unconnected-(U3-T1OUT-Pad14)") (class "Default")
      (node (ref "U3") (pin "14") (pinfunction "T1OUT_14") (pintype "output"))
    )
    (net (code "79") (name "unconnected-(U6-C-Pad2)") (class "Default")
      (node (ref "U6") (pin "2") (pinfunction "C_2") (pintype "passive"))
    )
    (net (code "80") (name "unconnected-(U6-D-Pad4)") (class "Default")
      (node (ref "U6") (pin "4") (pinfunction "D_4") (pintype "passive"))
    )
    (net (code "81") (name "unconnected-(U8-RESET-Pad3)") (class "Default")
      (node (ref "U8") (pin "3") (pinfunction "RESET_3") (pintype "output"))
    )
    (net (code "82") (name "unconnected-(U8-~{MR}-Pad4)") (class "Default")
      (node (ref "U8") (pin "4") (pinfunction "~{MR}_4") (pintype "input"))
    )
  )
)
